# Power_for_Slaves.net
KiCad netlist of a schematic drawn in Altium Designer
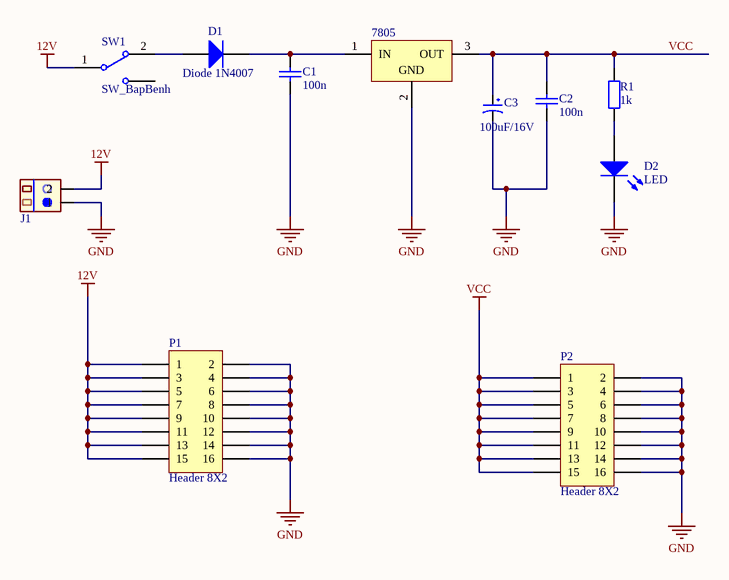
[diagram p0: Power for Slaves.SchDoc]

(export (version "E")
  (design (tool "Eeschema 10.0.6"))
  (components
    (comp (ref "7805")
      (value "L78M05CP")
      (footprint "QTO-220")
      (description "Positive Voltage Regulator")
      (fields (field (name "PUBLISHER") "Altium Limited"))
      (libsource (lib "syhaunguyen") (part "L78M05CP"))
    )
    (comp (ref "C1")
      (value "100n")
      (footprint "Cap Non-Pol 3mm")
      (description "Non-polarized Capacitor")
      (fields (field (name "Comment") "Cap Non-pol") (field (name "PUBLISHER") "Altium Limited"))
      (libsource (lib "THG") (part "Cap Non-pol"))
    )
    (comp (ref "C2")
      (value "100n")
      (footprint "Cap Non-Pol 3mm")
      (description "Non-polarized Capacitor")
      (fields (field (name "Comment") "Cap Non-pol") (field (name "PUBLISHER") "Altium Limited"))
      (libsource (lib "THG") (part "Cap Non-pol"))
    )
    (comp (ref "C3")
      (value "100uF/16V")
      (footprint "CP1.5/3.4")
      (description "Cap 100uF/35V - 470uF/16V")
      (libsource (lib "syhaunguyen") (part "CP3"))
    )
    (comp (ref "D1")
      (value "Diode 1N4007")
      (footprint "DO-41")
      (description "1 Amp General Purpose Rectifier")
      (fields (field (name "PUBLISHER") "Altium Limited"))
      (libsource (lib "hphonglib") (part "Diode 1N4007"))
    )
    (comp (ref "D2")
      (value "LED")
      (footprint "LED-5mm RED")
      (description "Typical LED")
      (fields (field (name "PUBLISHER") "Altium Limited"))
      (libsource (lib "THG") (part "LED"))
    )
    (comp (ref "J1")
      (value "CON.Domino2")
      (footprint "Domino 2M")
      (description "2 pins Domino Header")
      (fields (field (name "PUBLISHER") "Hoang Nguyen"))
      (libsource (lib "THG") (part "CON.Domino2"))
    )
    (comp (ref "P1")
      (value "Header 8X2")
      (footprint "HDR2X8")
      (description "Header, 8-Pin, Dual row")
      (fields (field (name "PUBLISHER") "Altium Limited"))
      (libsource (lib "Miscellaneous Connectors") (part "Header 8X2"))
    )
    (comp (ref "P2")
      (value "Header 8X2")
      (footprint "HDR2X8")
      (description "Header, 8-Pin, Dual row")
      (fields (field (name "PUBLISHER") "Altium Limited"))
      (libsource (lib "Miscellaneous Connectors") (part "Header 8X2"))
    )
    (comp (ref "R1")
      (value "1k")
      (footprint "RESISTOR 1/4W")
      (description "RES_0805")
      (fields (field (name "Comment") "RES_SMD_0805") (field (name "PUBLISHER") "Altium Limited"))
      (libsource (lib "THG") (part "RES_SMD_0805"))
    )
    (comp (ref "SW1")
      (value "SW_BapBenh")
      (footprint "SW_Bapbenh")
      (libsource (lib "THG") (part "SW_BapBenh"))
    )
  )
  (nets
    (net (code "1") (name "12V") (class "Default")
      (node (ref "J1") (pin "2") (pinfunction "2_2") (pintype "passive"))
      (node (ref "P1") (pin "1") (pinfunction "1_1") (pintype "passive"))
      (node (ref "P1") (pin "11") (pinfunction "11_11") (pintype "passive"))
      (node (ref "P1") (pin "13") (pinfunction "13_13") (pintype "passive"))
      (node (ref "P1") (pin "15") (pinfunction "15_15") (pintype "passive"))
      (node (ref "P1") (pin "3") (pinfunction "3_3") (pintype "passive"))
      (node (ref "P1") (pin "5") (pinfunction "5_5") (pintype "passive"))
      (node (ref "P1") (pin "7") (pinfunction "7_7") (pintype "passive"))
      (node (ref "P1") (pin "9") (pinfunction "9_9") (pintype "passive"))
      (node (ref "SW1") (pin "1") (pinfunction "1_1") (pintype "passive"))
    )
    (net (code "2") (name "GND") (class "Default")
      (node (ref "7805") (pin "2") (pinfunction "GND_2") (pintype "power_in"))
      (node (ref "C1") (pin "1") (pinfunction "1_1") (pintype "passive"))
      (node (ref "C2") (pin "1") (pinfunction "1_1") (pintype "passive"))
      (node (ref "C3") (pin "2") (pinfunction "2_2") (pintype "passive"))
      (node (ref "D2") (pin "2") (pinfunction "K_2") (pintype "passive"))
      (node (ref "J1") (pin "1") (pinfunction "1_1") (pintype "passive"))
      (node (ref "P1") (pin "10") (pinfunction "10_10") (pintype "passive"))
      (node (ref "P1") (pin "12") (pinfunction "12_12") (pintype "passive"))
      (node (ref "P1") (pin "14") (pinfunction "14_14") (pintype "passive"))
      (node (ref "P1") (pin "16") (pinfunction "16_16") (pintype "passive"))
      (node (ref "P1") (pin "2") (pinfunction "2_2") (pintype "passive"))
      (node (ref "P1") (pin "4") (pinfunction "4_4") (pintype "passive"))
      (node (ref "P1") (pin "6") (pinfunction "6_6") (pintype "passive"))
      (node (ref "P1") (pin "8") (pinfunction "8_8") (pintype "passive"))
      (node (ref "P2") (pin "10") (pinfunction "10_10") (pintype "passive"))
      (node (ref "P2") (pin "12") (pinfunction "12_12") (pintype "passive"))
      (node (ref "P2") (pin "14") (pinfunction "14_14") (pintype "passive"))
      (node (ref "P2") (pin "16") (pinfunction "16_16") (pintype "passive"))
      (node (ref "P2") (pin "2") (pinfunction "2_2") (pintype "passive"))
      (node (ref "P2") (pin "4") (pinfunction "4_4") (pintype "passive"))
      (node (ref "P2") (pin "6") (pinfunction "6_6") (pintype "passive"))
      (node (ref "P2") (pin "8") (pinfunction "8_8") (pintype "passive"))
    )
    (net (code "3") (name "Net-(7805-IN)") (class "Default")
      (node (ref "7805") (pin "1") (pinfunction "IN_1") (pintype "power_in"))
      (node (ref "C1") (pin "2") (pinfunction "2_2") (pintype "passive"))
      (node (ref "D1") (pin "2") (pinfunction "K_2") (pintype "passive"))
    )
    (net (code "4") (name "Net-(D1-A)") (class "Default")
      (node (ref "D1") (pin "1") (pinfunction "A_1") (pintype "passive"))
      (node (ref "SW1") (pin "2") (pinfunction "2_2") (pintype "passive"))
    )
    (net (code "5") (name "Net-(D2-A)") (class "Default")
      (node (ref "D2") (pin "1") (pinfunction "A_1") (pintype "passive"))
      (node (ref "R1") (pin "1") (pinfunction "1_1") (pintype "passive"))
    )
    (net (code "6") (name "VCC") (class "Default")
      (node (ref "7805") (pin "3") (pinfunction "OUT_3") (pintype "power_in"))
      (node (ref "C2") (pin "2") (pinfunction "2_2") (pintype "passive"))
      (node (ref "C3") (pin "1") (pinfunction "1_1") (pintype "passive"))
      (node (ref "P2") (pin "1") (pinfunction "1_1") (pintype "passive"))
      (node (ref "P2") (pin "11") (pinfunction "11_11") (pintype "passive"))
      (node (ref "P2") (pin "13") (pinfunction "13_13") (pintype "passive"))
      (node (ref "P2") (pin "15") (pinfunction "15_15") (pintype "passive"))
      (node (ref "P2") (pin "3") (pinfunction "3_3") (pintype "passive"))
      (node (ref "P2") (pin "5") (pinfunction "5_5") (pintype "passive"))
      (node (ref "P2") (pin "7") (pinfunction "7_7") (pintype "passive"))
      (node (ref "P2") (pin "9") (pinfunction "9_9") (pintype "passive"))
      (node (ref "R1") (pin "2") (pinfunction "2_2") (pintype "passive"))
    )
  )
)
